# ESP32_ADC_DAC.net
KiCad netlist of a schematic drawn in Altium Designer
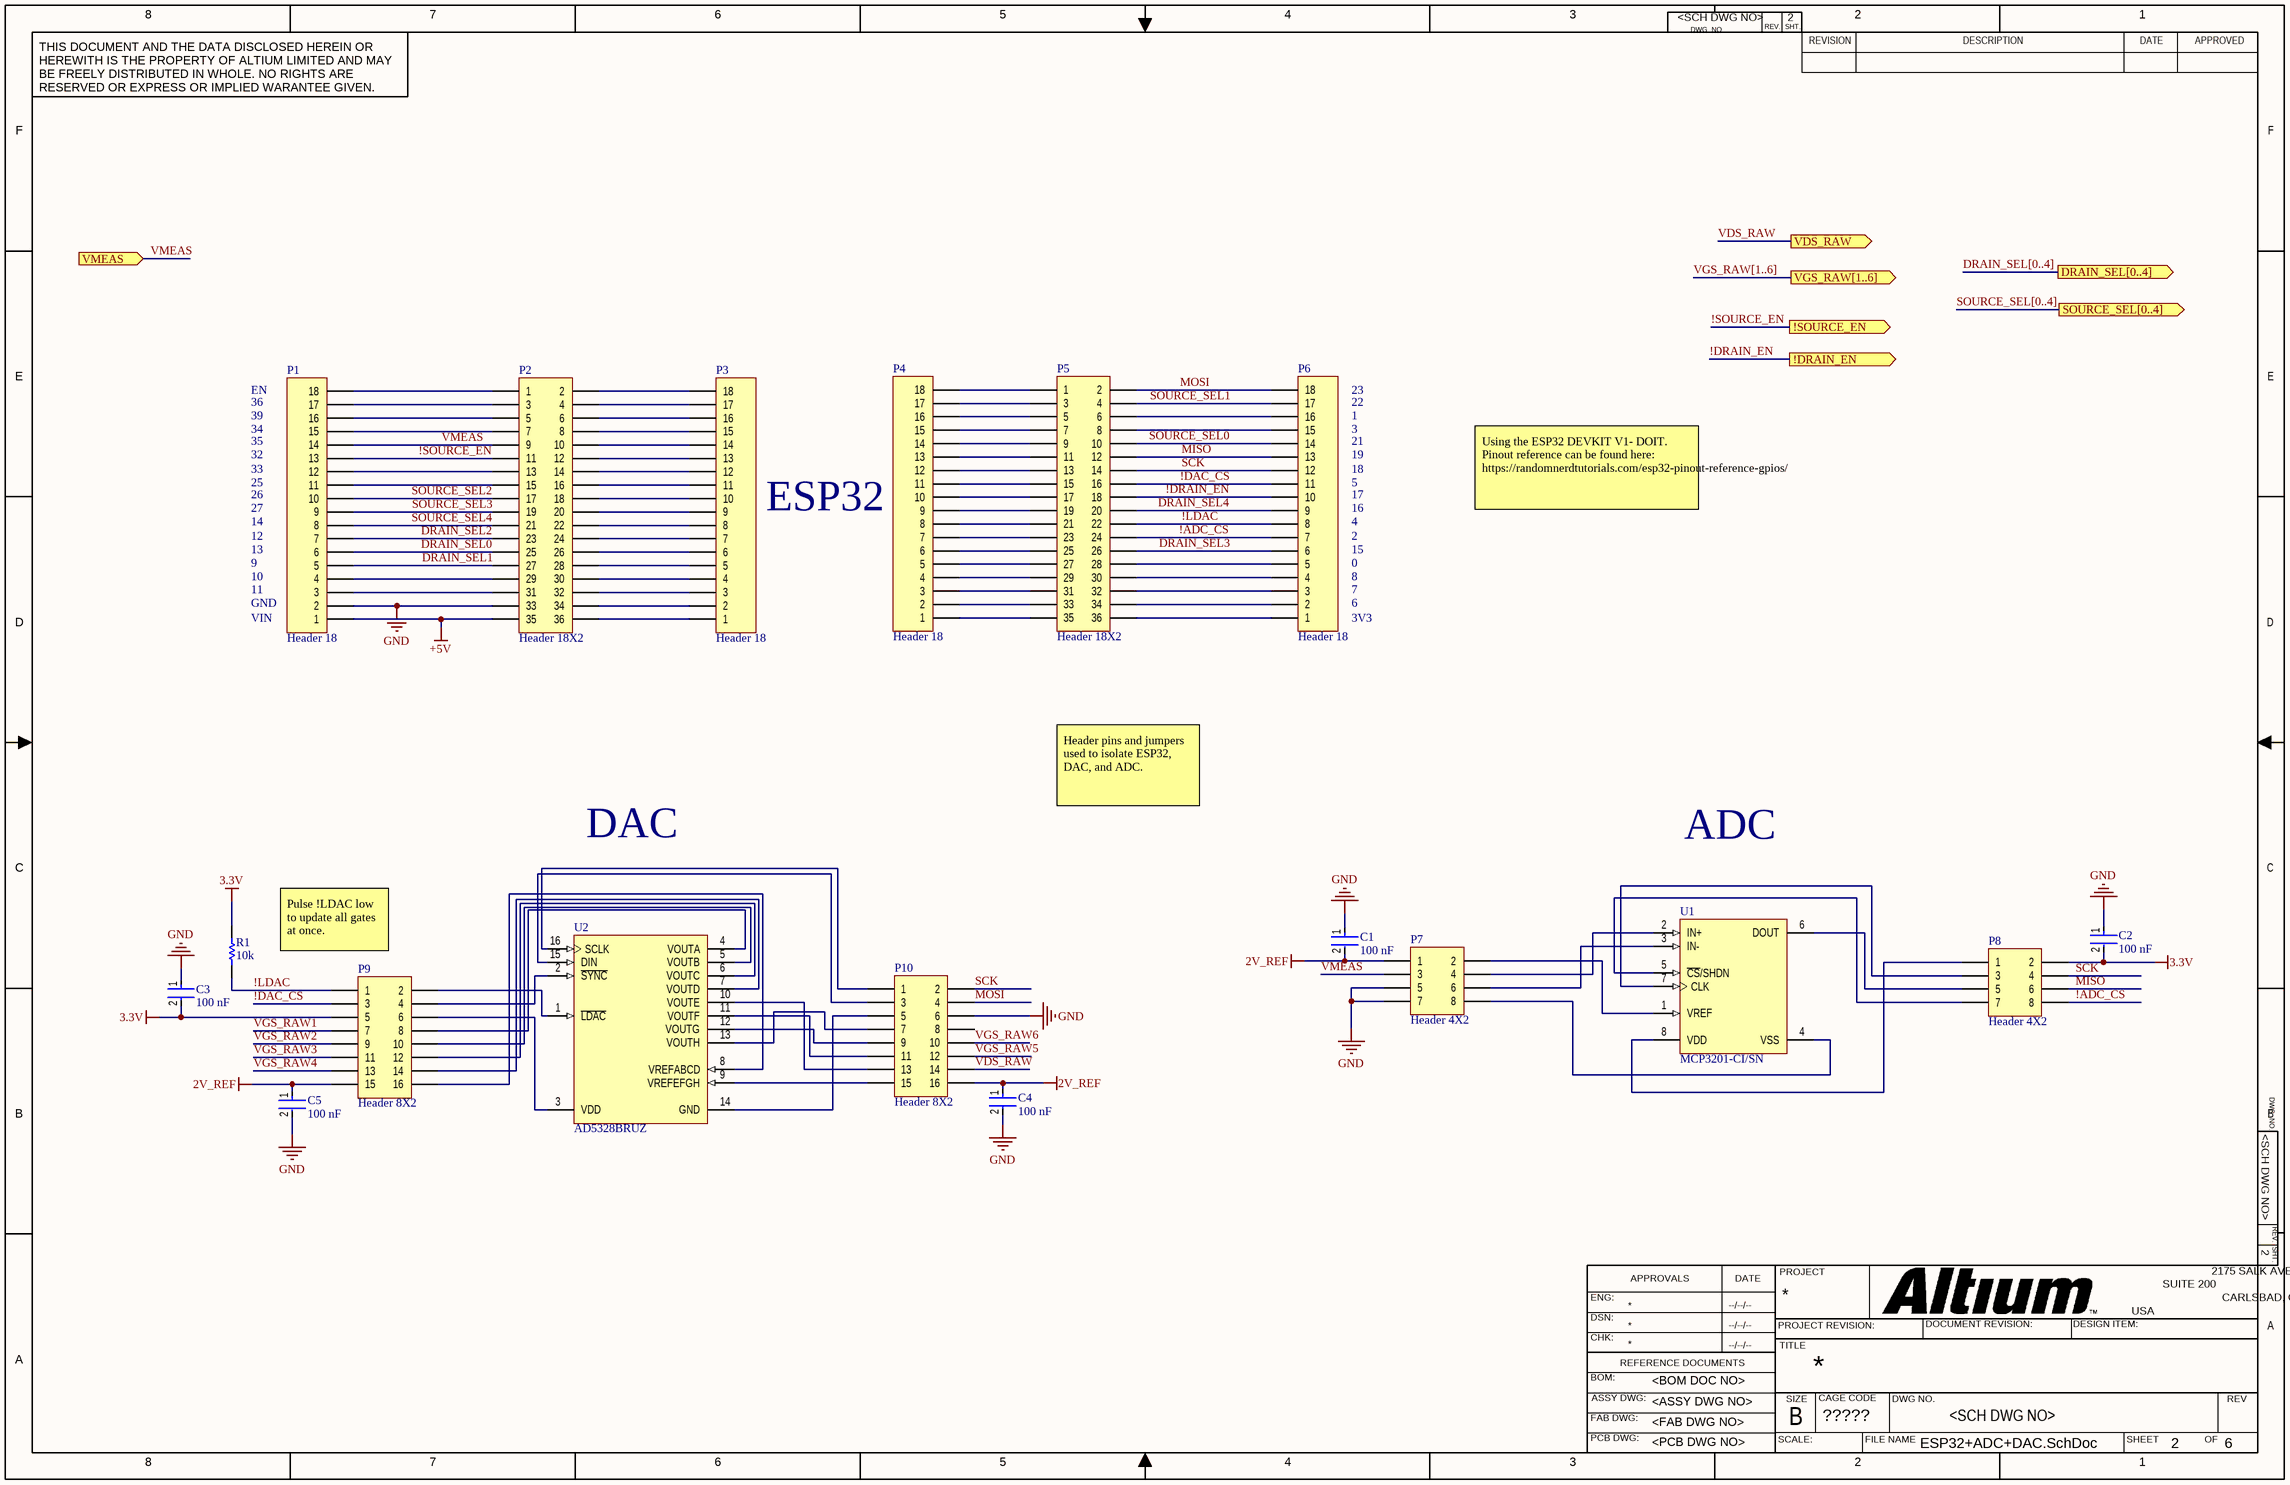
[diagram p0: ESP32+ADC+DAC.SchDoc]

(export (version "E")
  (design (tool "Eeschema 10.0.6"))
  (components
    (comp (ref "C1")
      (value "100 nF")
      (footprint "FP-C0805C-DN-MFG")
      (description "CAP CER 0.1UF 50V X7R 0805")
      (fields
        (field (name "MANUFACTURER PART NUMBER") "C0805C104K5RACTU")
        (field (name "MANUFACTURER") "KEMET")
      )
      (libsource (lib "Altium Content Vault") (part "b4654b650e69147ec39a6b967a45e02"))
    )
    (comp (ref "C2")
      (value "100 nF")
      (footprint "FP-C0805C-DN-MFG")
      (description "CAP CER 0.1UF 50V X7R 0805")
      (fields
        (field (name "MANUFACTURER PART NUMBER") "C0805C104K5RACTU")
        (field (name "MANUFACTURER") "KEMET")
      )
      (libsource (lib "Altium Content Vault") (part "b4654b650e69147ec39a6b967a45e02"))
    )
    (comp (ref "C3")
      (value "100 nF")
      (footprint "FP-C0805C-DN-MFG")
      (description "CAP CER 0.1UF 50V X7R 0805")
      (fields
        (field (name "MANUFACTURER PART NUMBER") "C0805C104K5RACTU")
        (field (name "MANUFACTURER") "KEMET")
      )
      (libsource (lib "Altium Content Vault") (part "b4654b650e69147ec39a6b967a45e02"))
    )
    (comp (ref "C4")
      (value "100 nF")
      (footprint "FP-C0805C-DN-MFG")
      (description "CAP CER 0.1UF 50V X7R 0805")
      (fields
        (field (name "MANUFACTURER PART NUMBER") "C0805C104K5RACTU")
        (field (name "MANUFACTURER") "KEMET")
      )
      (libsource (lib "Altium Content Vault") (part "b4654b650e69147ec39a6b967a45e02"))
    )
    (comp (ref "C5")
      (value "100 nF")
      (footprint "FP-C0805C-DN-MFG")
      (description "CAP CER 0.1UF 50V X7R 0805")
      (fields
        (field (name "MANUFACTURER PART NUMBER") "C0805C104K5RACTU")
        (field (name "MANUFACTURER") "KEMET")
      )
      (libsource (lib "Altium Content Vault") (part "b4654b650e69147ec39a6b967a45e02"))
    )
    (comp (ref "P1")
      (value "Header 18")
      (footprint "HDR1X18")
      (description "Header, 18-Pin")
      (fields (field (name "PUBLISHER") "Altium Limited"))
      (libsource (lib "") (part "Header 18_1"))
    )
    (comp (ref "P2")
      (value "Header 18X2")
      (footprint "HDR2X18")
      (description "Header, 18-Pin, Dual row")
      (fields (field (name "PUBLISHER") "Altium Limited"))
      (libsource (lib "Miscellaneous Connectors") (part "Header 18X2"))
    )
    (comp (ref "P3")
      (value "Header 18")
      (footprint "HDR1X18")
      (description "Header, 18-Pin")
      (fields (field (name "PUBLISHER") "Altium Limited"))
      (libsource (lib "Miscellaneous Connectors") (part "Header 18"))
    )
    (comp (ref "P4")
      (value "Header 18")
      (footprint "HDR1X18")
      (description "Header, 18-Pin")
      (fields (field (name "PUBLISHER") "Altium Limited"))
      (libsource (lib "") (part "Header 18_1"))
    )
    (comp (ref "P5")
      (value "Header 18X2")
      (footprint "HDR2X18")
      (description "Header, 18-Pin, Dual row")
      (fields (field (name "PUBLISHER") "Altium Limited"))
      (libsource (lib "Miscellaneous Connectors") (part "Header 18X2"))
    )
    (comp (ref "P6")
      (value "Header 18")
      (footprint "HDR1X18")
      (description "Header, 18-Pin")
      (fields (field (name "PUBLISHER") "Altium Limited"))
      (libsource (lib "Miscellaneous Connectors") (part "Header 18"))
    )
    (comp (ref "P7")
      (value "Header 4X2")
      (footprint "HDR2X4")
      (description "Header, 4-Pin, Dual row")
      (fields (field (name "PUBLISHER") "Altium Limited"))
      (libsource (lib "Miscellaneous Connectors") (part "Header 4X2"))
    )
    (comp (ref "P8")
      (value "Header 4X2")
      (footprint "HDR2X4")
      (description "Header, 4-Pin, Dual row")
      (fields (field (name "PUBLISHER") "Altium Limited"))
      (libsource (lib "Miscellaneous Connectors") (part "Header 4X2"))
    )
    (comp (ref "P9")
      (value "Header 8X2")
      (footprint "HDR2X8")
      (description "Header, 8-Pin, Dual row")
      (fields (field (name "PUBLISHER") "Altium Limited"))
      (libsource (lib "Miscellaneous Connectors") (part "Header 8X2"))
    )
    (comp (ref "P10")
      (value "Header 8X2")
      (footprint "HDR2X8")
      (description "Header, 8-Pin, Dual row")
      (fields (field (name "PUBLISHER") "Altium Limited"))
      (libsource (lib "Miscellaneous Connectors") (part "Header 8X2"))
    )
    (comp (ref "R1")
      (value "10k")
      (footprint "RESC2013X60X35NL10T20")
      (description "Chip Resistor, 10 KOhm, +/- 1%, 0.125 W, -55 to 155 degC, 0805 (2012 Metric), RoHS, Tape and Reel")
      (fields (field (name "MANUFACTURER") "Yageo"))
      (libsource (lib "Altium Content Vault") (part "RES-2"))
    )
    (comp (ref "U1")
      (value "MCP3201-CI/SN")
      (footprint "SOIC-SN8_L")
      (libsource (lib "Altium Content Vault") (part "CON-ADC-MCP3001-8"))
    )
    (comp (ref "U2")
      (value "AD5328BRUZ")
      (footprint "RU-16_L")
      (fields (field (name "GENERIC PART NUMBER") "AD5328") (field (name "MANUFACTURER") "Analog Devices"))
      (libsource (lib "Altium Content Vault") (part "ADI-AD5328-RU-16"))
    )
  )
  (nets
    (net (code "1") (name "+5V") (class "Default")
      (node (ref "P1") (pin "1") (pinfunction "1_1") (pintype "passive"))
      (node (ref "P2") (pin "35") (pinfunction "35_35") (pintype "passive"))
    )
    (net (code "2") (name "/!ADC_CS") (class "Default")
      (node (ref "P5") (pin "24") (pinfunction "24_24") (pintype "passive"))
      (node (ref "P6") (pin "7") (pinfunction "7_7") (pintype "passive"))
      (node (ref "P8") (pin "8") (pinfunction "8_8") (pintype "passive"))
    )
    (net (code "3") (name "/!DAC_CS") (class "Default")
      (node (ref "P5") (pin "16") (pinfunction "16_16") (pintype "passive"))
      (node (ref "P6") (pin "11") (pinfunction "11_11") (pintype "passive"))
      (node (ref "P9") (pin "3") (pinfunction "3_3") (pintype "passive"))
    )
    (net (code "4") (name "/!DRAIN_EN") (class "Default")
      (node (ref "P5") (pin "18") (pinfunction "18_18") (pintype "passive"))
      (node (ref "P6") (pin "10") (pinfunction "10_10") (pintype "passive"))
    )
    (net (code "5") (name "/!LDAC") (class "Default")
      (node (ref "P5") (pin "22") (pinfunction "22_22") (pintype "passive"))
      (node (ref "P6") (pin "8") (pinfunction "8_8") (pintype "passive"))
      (node (ref "P9") (pin "1") (pinfunction "1_1") (pintype "passive"))
      (node (ref "R1") (pin "1") (pinfunction "1_1") (pintype "passive"))
    )
    (net (code "6") (name "/!SOURCE_EN") (class "Default")
      (node (ref "P1") (pin "13") (pinfunction "13_13") (pintype "passive"))
      (node (ref "P2") (pin "11") (pinfunction "11_11") (pintype "passive"))
    )
    (net (code "7") (name "/DRAIN_SEL0") (class "Default")
      (node (ref "P1") (pin "6") (pinfunction "6_6") (pintype "passive"))
      (node (ref "P2") (pin "25") (pinfunction "25_25") (pintype "passive"))
    )
    (net (code "8") (name "/DRAIN_SEL1") (class "Default")
      (node (ref "P1") (pin "5") (pinfunction "5_5") (pintype "passive"))
      (node (ref "P2") (pin "27") (pinfunction "27_27") (pintype "passive"))
    )
    (net (code "9") (name "/DRAIN_SEL2") (class "Default")
      (node (ref "P1") (pin "7") (pinfunction "7_7") (pintype "passive"))
      (node (ref "P2") (pin "23") (pinfunction "23_23") (pintype "passive"))
    )
    (net (code "10") (name "/DRAIN_SEL3") (class "Default")
      (node (ref "P5") (pin "26") (pinfunction "26_26") (pintype "passive"))
      (node (ref "P6") (pin "6") (pinfunction "6_6") (pintype "passive"))
    )
    (net (code "11") (name "/DRAIN_SEL4") (class "Default")
      (node (ref "P5") (pin "20") (pinfunction "20_20") (pintype "passive"))
      (node (ref "P6") (pin "9") (pinfunction "9_9") (pintype "passive"))
    )
    (net (code "13") (name "/MISO") (class "Default")
      (node (ref "P5") (pin "12") (pinfunction "12_12") (pintype "passive"))
      (node (ref "P6") (pin "13") (pinfunction "13_13") (pintype "passive"))
      (node (ref "P8") (pin "6") (pinfunction "6_6") (pintype "passive"))
    )
    (net (code "14") (name "/MOSI") (class "Default")
      (node (ref "P10") (pin "4") (pinfunction "4_4") (pintype "passive"))
      (node (ref "P5") (pin "2") (pinfunction "2_2") (pintype "passive"))
      (node (ref "P6") (pin "18") (pinfunction "18_18") (pintype "passive"))
    )
    (net (code "15") (name "/SCK") (class "Default")
      (node (ref "P10") (pin "2") (pinfunction "2_2") (pintype "passive"))
      (node (ref "P5") (pin "14") (pinfunction "14_14") (pintype "passive"))
      (node (ref "P6") (pin "12") (pinfunction "12_12") (pintype "passive"))
      (node (ref "P8") (pin "4") (pinfunction "4_4") (pintype "passive"))
    )
    (net (code "16") (name "/SOURCE_SEL0") (class "Default")
      (node (ref "P5") (pin "10") (pinfunction "10_10") (pintype "passive"))
      (node (ref "P6") (pin "14") (pinfunction "14_14") (pintype "passive"))
    )
    (net (code "17") (name "/SOURCE_SEL1") (class "Default")
      (node (ref "P5") (pin "4") (pinfunction "4_4") (pintype "passive"))
      (node (ref "P6") (pin "17") (pinfunction "17_17") (pintype "passive"))
    )
    (net (code "18") (name "/SOURCE_SEL2") (class "Default")
      (node (ref "P1") (pin "10") (pinfunction "10_10") (pintype "passive"))
      (node (ref "P2") (pin "17") (pinfunction "17_17") (pintype "passive"))
    )
    (net (code "19") (name "/SOURCE_SEL3") (class "Default")
      (node (ref "P1") (pin "9") (pinfunction "9_9") (pintype "passive"))
      (node (ref "P2") (pin "19") (pinfunction "19_19") (pintype "passive"))
    )
    (net (code "20") (name "/SOURCE_SEL4") (class "Default")
      (node (ref "P1") (pin "8") (pinfunction "8_8") (pintype "passive"))
      (node (ref "P2") (pin "21") (pinfunction "21_21") (pintype "passive"))
    )
    (net (code "22") (name "/VDS_RAW") (class "Default")
      (node (ref "P10") (pin "14") (pinfunction "14_14") (pintype "passive"))
    )
    (net (code "23") (name "/VGS_RAW1") (class "Default")
      (node (ref "P9") (pin "7") (pinfunction "7_7") (pintype "passive"))
    )
    (net (code "24") (name "/VGS_RAW2") (class "Default")
      (node (ref "P9") (pin "9") (pinfunction "9_9") (pintype "passive"))
    )
    (net (code "25") (name "/VGS_RAW3") (class "Default")
      (node (ref "P9") (pin "11") (pinfunction "11_11") (pintype "passive"))
    )
    (net (code "26") (name "/VGS_RAW4") (class "Default")
      (node (ref "P9") (pin "13") (pinfunction "13_13") (pintype "passive"))
    )
    (net (code "27") (name "/VGS_RAW5") (class "Default")
      (node (ref "P10") (pin "12") (pinfunction "12_12") (pintype "passive"))
    )
    (net (code "28") (name "/VGS_RAW6") (class "Default")
      (node (ref "P10") (pin "10") (pinfunction "10_10") (pintype "passive"))
    )
    (net (code "30") (name "/VMEAS") (class "Default")
      (node (ref "P1") (pin "14") (pinfunction "14_14") (pintype "passive"))
      (node (ref "P2") (pin "9") (pinfunction "9_9") (pintype "passive"))
      (node (ref "P7") (pin "3") (pinfunction "3_3") (pintype "passive"))
    )
    (net (code "31") (name "2V_REF") (class "Default")
      (node (ref "C1") (pin "2") (pinfunction "2_2") (pintype "passive"))
      (node (ref "C4") (pin "1") (pinfunction "1_1") (pintype "passive"))
      (node (ref "C5") (pin "1") (pinfunction "1_1") (pintype "passive"))
      (node (ref "P10") (pin "16") (pinfunction "16_16") (pintype "passive"))
      (node (ref "P7") (pin "1") (pinfunction "1_1") (pintype "passive"))
      (node (ref "P9") (pin "15") (pinfunction "15_15") (pintype "passive"))
    )
    (net (code "32") (name "3.3V") (class "Default")
      (node (ref "C2") (pin "2") (pinfunction "2_2") (pintype "passive"))
      (node (ref "C3") (pin "2") (pinfunction "2_2") (pintype "passive"))
      (node (ref "P8") (pin "2") (pinfunction "2_2") (pintype "passive"))
      (node (ref "P9") (pin "5") (pinfunction "5_5") (pintype "passive"))
      (node (ref "R1") (pin "2") (pinfunction "2_2") (pintype "passive"))
    )
    (net (code "33") (name "GND") (class "Default")
      (node (ref "C1") (pin "1") (pinfunction "1_1") (pintype "passive"))
      (node (ref "C2") (pin "1") (pinfunction "1_1") (pintype "passive"))
      (node (ref "C3") (pin "1") (pinfunction "1_1") (pintype "passive"))
      (node (ref "C4") (pin "2") (pinfunction "2_2") (pintype "passive"))
      (node (ref "C5") (pin "2") (pinfunction "2_2") (pintype "passive"))
      (node (ref "P1") (pin "2") (pinfunction "2_2") (pintype "passive"))
      (node (ref "P10") (pin "6") (pinfunction "6_6") (pintype "passive"))
      (node (ref "P2") (pin "33") (pinfunction "33_33") (pintype "passive"))
      (node (ref "P7") (pin "5") (pinfunction "5_5") (pintype "passive"))
      (node (ref "P7") (pin "7") (pinfunction "7_7") (pintype "passive"))
    )
    (net (code "34") (name "Net-(P1-Pad3)") (class "Default")
      (node (ref "P1") (pin "3") (pinfunction "3_3") (pintype "passive"))
      (node (ref "P2") (pin "31") (pinfunction "31_31") (pintype "passive"))
    )
    (net (code "35") (name "Net-(P1-Pad4)") (class "Default")
      (node (ref "P1") (pin "4") (pinfunction "4_4") (pintype "passive"))
      (node (ref "P2") (pin "29") (pinfunction "29_29") (pintype "passive"))
    )
    (net (code "36") (name "Net-(P1-Pad11)") (class "Default")
      (node (ref "P1") (pin "11") (pinfunction "11_11") (pintype "passive"))
      (node (ref "P2") (pin "15") (pinfunction "15_15") (pintype "passive"))
    )
    (net (code "37") (name "Net-(P1-Pad12)") (class "Default")
      (node (ref "P1") (pin "12") (pinfunction "12_12") (pintype "passive"))
      (node (ref "P2") (pin "13") (pinfunction "13_13") (pintype "passive"))
    )
    (net (code "38") (name "Net-(P1-Pad15)") (class "Default")
      (node (ref "P1") (pin "15") (pinfunction "15_15") (pintype "passive"))
      (node (ref "P2") (pin "7") (pinfunction "7_7") (pintype "passive"))
    )
    (net (code "39") (name "Net-(P1-Pad16)") (class "Default")
      (node (ref "P1") (pin "16") (pinfunction "16_16") (pintype "passive"))
      (node (ref "P2") (pin "5") (pinfunction "5_5") (pintype "passive"))
    )
    (net (code "40") (name "Net-(P1-Pad17)") (class "Default")
      (node (ref "P1") (pin "17") (pinfunction "17_17") (pintype "passive"))
      (node (ref "P2") (pin "3") (pinfunction "3_3") (pintype "passive"))
    )
    (net (code "41") (name "Net-(P1-Pad18)") (class "Default")
      (node (ref "P1") (pin "18") (pinfunction "18_18") (pintype "passive"))
      (node (ref "P2") (pin "1") (pinfunction "1_1") (pintype "passive"))
    )
    (net (code "42") (name "Net-(P2-Pad2)") (class "Default")
      (node (ref "P2") (pin "2") (pinfunction "2_2") (pintype "passive"))
      (node (ref "P3") (pin "18") (pinfunction "18_18") (pintype "passive"))
    )
    (net (code "43") (name "Net-(P2-Pad4)") (class "Default")
      (node (ref "P2") (pin "4") (pinfunction "4_4") (pintype "passive"))
      (node (ref "P3") (pin "17") (pinfunction "17_17") (pintype "passive"))
    )
    (net (code "44") (name "Net-(P2-Pad6)") (class "Default")
      (node (ref "P2") (pin "6") (pinfunction "6_6") (pintype "passive"))
      (node (ref "P3") (pin "16") (pinfunction "16_16") (pintype "passive"))
    )
    (net (code "45") (name "Net-(P2-Pad8)") (class "Default")
      (node (ref "P2") (pin "8") (pinfunction "8_8") (pintype "passive"))
      (node (ref "P3") (pin "15") (pinfunction "15_15") (pintype "passive"))
    )
    (net (code "46") (name "Net-(P2-Pad10)") (class "Default")
      (node (ref "P2") (pin "10") (pinfunction "10_10") (pintype "passive"))
      (node (ref "P3") (pin "14") (pinfunction "14_14") (pintype "passive"))
    )
    (net (code "47") (name "Net-(P2-Pad12)") (class "Default")
      (node (ref "P2") (pin "12") (pinfunction "12_12") (pintype "passive"))
      (node (ref "P3") (pin "13") (pinfunction "13_13") (pintype "passive"))
    )
    (net (code "48") (name "Net-(P2-Pad14)") (class "Default")
      (node (ref "P2") (pin "14") (pinfunction "14_14") (pintype "passive"))
      (node (ref "P3") (pin "12") (pinfunction "12_12") (pintype "passive"))
    )
    (net (code "49") (name "Net-(P2-Pad16)") (class "Default")
      (node (ref "P2") (pin "16") (pinfunction "16_16") (pintype "passive"))
      (node (ref "P3") (pin "11") (pinfunction "11_11") (pintype "passive"))
    )
    (net (code "50") (name "Net-(P2-Pad18)") (class "Default")
      (node (ref "P2") (pin "18") (pinfunction "18_18") (pintype "passive"))
      (node (ref "P3") (pin "10") (pinfunction "10_10") (pintype "passive"))
    )
    (net (code "51") (name "Net-(P2-Pad20)") (class "Default")
      (node (ref "P2") (pin "20") (pinfunction "20_20") (pintype "passive"))
      (node (ref "P3") (pin "9") (pinfunction "9_9") (pintype "passive"))
    )
    (net (code "52") (name "Net-(P2-Pad22)") (class "Default")
      (node (ref "P2") (pin "22") (pinfunction "22_22") (pintype "passive"))
      (node (ref "P3") (pin "8") (pinfunction "8_8") (pintype "passive"))
    )
    (net (code "53") (name "Net-(P2-Pad24)") (class "Default")
      (node (ref "P2") (pin "24") (pinfunction "24_24") (pintype "passive"))
      (node (ref "P3") (pin "7") (pinfunction "7_7") (pintype "passive"))
    )
    (net (code "54") (name "Net-(P2-Pad26)") (class "Default")
      (node (ref "P2") (pin "26") (pinfunction "26_26") (pintype "passive"))
      (node (ref "P3") (pin "6") (pinfunction "6_6") (pintype "passive"))
    )
    (net (code "55") (name "Net-(P2-Pad28)") (class "Default")
      (node (ref "P2") (pin "28") (pinfunction "28_28") (pintype "passive"))
      (node (ref "P3") (pin "5") (pinfunction "5_5") (pintype "passive"))
    )
    (net (code "56") (name "Net-(P2-Pad30)") (class "Default")
      (node (ref "P2") (pin "30") (pinfunction "30_30") (pintype "passive"))
      (node (ref "P3") (pin "4") (pinfunction "4_4") (pintype "passive"))
    )
    (net (code "57") (name "Net-(P2-Pad32)") (class "Default")
      (node (ref "P2") (pin "32") (pinfunction "32_32") (pintype "passive"))
      (node (ref "P3") (pin "3") (pinfunction "3_3") (pintype "passive"))
    )
    (net (code "58") (name "Net-(P2-Pad34)") (class "Default")
      (node (ref "P2") (pin "34") (pinfunction "34_34") (pintype "passive"))
      (node (ref "P3") (pin "2") (pinfunction "2_2") (pintype "passive"))
    )
    (net (code "59") (name "Net-(P2-Pad36)") (class "Default")
      (node (ref "P2") (pin "36") (pinfunction "36_36") (pintype "passive"))
      (node (ref "P3") (pin "1") (pinfunction "1_1") (pintype "passive"))
    )
    (net (code "60") (name "Net-(P4-Pad1)") (class "Default")
      (node (ref "P4") (pin "1") (pinfunction "1_1") (pintype "passive"))
      (node (ref "P5") (pin "35") (pinfunction "35_35") (pintype "passive"))
    )
    (net (code "61") (name "Net-(P4-Pad2)") (class "Default")
      (node (ref "P4") (pin "2") (pinfunction "2_2") (pintype "passive"))
      (node (ref "P5") (pin "33") (pinfunction "33_33") (pintype "passive"))
    )
    (net (code "62") (name "Net-(P4-Pad3)") (class "Default")
      (node (ref "P4") (pin "3") (pinfunction "3_3") (pintype "passive"))
      (node (ref "P5") (pin "31") (pinfunction "31_31") (pintype "passive"))
    )
    (net (code "63") (name "Net-(P4-Pad4)") (class "Default")
      (node (ref "P4") (pin "4") (pinfunction "4_4") (pintype "passive"))
      (node (ref "P5") (pin "29") (pinfunction "29_29") (pintype "passive"))
    )
    (net (code "64") (name "Net-(P4-Pad5)") (class "Default")
      (node (ref "P4") (pin "5") (pinfunction "5_5") (pintype "passive"))
      (node (ref "P5") (pin "27") (pinfunction "27_27") (pintype "passive"))
    )
    (net (code "65") (name "Net-(P4-Pad6)") (class "Default")
      (node (ref "P4") (pin "6") (pinfunction "6_6") (pintype "passive"))
      (node (ref "P5") (pin "25") (pinfunction "25_25") (pintype "passive"))
    )
    (net (code "66") (name "Net-(P4-Pad7)") (class "Default")
      (node (ref "P4") (pin "7") (pinfunction "7_7") (pintype "passive"))
      (node (ref "P5") (pin "23") (pinfunction "23_23") (pintype "passive"))
    )
    (net (code "67") (name "Net-(P4-Pad8)") (class "Default")
      (node (ref "P4") (pin "8") (pinfunction "8_8") (pintype "passive"))
      (node (ref "P5") (pin "21") (pinfunction "21_21") (pintype "passive"))
    )
    (net (code "68") (name "Net-(P4-Pad9)") (class "Default")
      (node (ref "P4") (pin "9") (pinfunction "9_9") (pintype "passive"))
      (node (ref "P5") (pin "19") (pinfunction "19_19") (pintype "passive"))
    )
    (net (code "69") (name "Net-(P4-Pad10)") (class "Default")
      (node (ref "P4") (pin "10") (pinfunction "10_10") (pintype "passive"))
      (node (ref "P5") (pin "17") (pinfunction "17_17") (pintype "passive"))
    )
    (net (code "70") (name "Net-(P4-Pad11)") (class "Default")
      (node (ref "P4") (pin "11") (pinfunction "11_11") (pintype "passive"))
      (node (ref "P5") (pin "15") (pinfunction "15_15") (pintype "passive"))
    )
    (net (code "71") (name "Net-(P4-Pad12)") (class "Default")
      (node (ref "P4") (pin "12") (pinfunction "12_12") (pintype "passive"))
      (node (ref "P5") (pin "13") (pinfunction "13_13") (pintype "passive"))
    )
    (net (code "72") (name "Net-(P4-Pad13)") (class "Default")
      (node (ref "P4") (pin "13") (pinfunction "13_13") (pintype "passive"))
      (node (ref "P5") (pin "11") (pinfunction "11_11") (pintype "passive"))
    )
    (net (code "73") (name "Net-(P4-Pad14)") (class "Default")
      (node (ref "P4") (pin "14") (pinfunction "14_14") (pintype "passive"))
      (node (ref "P5") (pin "9") (pinfunction "9_9") (pintype "passive"))
    )
    (net (code "74") (name "Net-(P4-Pad15)") (class "Default")
      (node (ref "P4") (pin "15") (pinfunction "15_15") (pintype "passive"))
      (node (ref "P5") (pin "7") (pinfunction "7_7") (pintype "passive"))
    )
    (net (code "75") (name "Net-(P4-Pad16)") (class "Default")
      (node (ref "P4") (pin "16") (pinfunction "16_16") (pintype "passive"))
      (node (ref "P5") (pin "5") (pinfunction "5_5") (pintype "passive"))
    )
    (net (code "76") (name "Net-(P4-Pad17)") (class "Default")
      (node (ref "P4") (pin "17") (pinfunction "17_17") (pintype "passive"))
      (node (ref "P5") (pin "3") (pinfunction "3_3") (pintype "passive"))
    )
    (net (code "77") (name "Net-(P4-Pad18)") (class "Default")
      (node (ref "P4") (pin "18") (pinfunction "18_18") (pintype "passive"))
      (node (ref "P5") (pin "1") (pinfunction "1_1") (pintype "passive"))
    )
    (net (code "78") (name "Net-(P5-Pad6)") (class "Default")
      (node (ref "P5") (pin "6") (pinfunction "6_6") (pintype "passive"))
      (node (ref "P6") (pin "16") (pinfunction "16_16") (pintype "passive"))
    )
    (net (code "79") (name "Net-(P5-Pad8)") (class "Default")
      (node (ref "P5") (pin "8") (pinfunction "8_8") (pintype "passive"))
      (node (ref "P6") (pin "15") (pinfunction "15_15") (pintype "passive"))
    )
    (net (code "80") (name "Net-(P5-Pad28)") (class "Default")
      (node (ref "P5") (pin "28") (pinfunction "28_28") (pintype "passive"))
      (node (ref "P6") (pin "5") (pinfunction "5_5") (pintype "passive"))
    )
    (net (code "81") (name "Net-(P5-Pad30)") (class "Default")
      (node (ref "P5") (pin "30") (pinfunction "30_30") (pintype "passive"))
      (node (ref "P6") (pin "4") (pinfunction "4_4") (pintype "passive"))
    )
    (net (code "82") (name "Net-(P5-Pad32)") (class "Default")
      (node (ref "P5") (pin "32") (pinfunction "32_32") (pintype "passive"))
      (node (ref "P6") (pin "3") (pinfunction "3_3") (pintype "passive"))
    )
    (net (code "83") (name "Net-(P5-Pad34)") (class "Default")
      (node (ref "P5") (pin "34") (pinfunction "34_34") (pintype "passive"))
      (node (ref "P6") (pin "2") (pinfunction "2_2") (pintype "passive"))
    )
    (net (code "84") (name "Net-(P5-Pad36)") (class "Default")
      (node (ref "P5") (pin "36") (pinfunction "36_36") (pintype "passive"))
      (node (ref "P6") (pin "1") (pinfunction "1_1") (pintype "passive"))
    )
    (net (code "85") (name "Net-(U1-CLK)") (class "Default")
      (node (ref "P8") (pin "3") (pinfunction "3_3") (pintype "passive"))
      (node (ref "U1") (pin "7") (pinfunction "CLK_7") (pintype "input"))
    )
    (net (code "86") (name "Net-(U1-DOUT)") (class "Default")
      (node (ref "P8") (pin "5") (pinfunction "5_5") (pintype "passive"))
      (node (ref "U1") (pin "6") (pinfunction "DOUT_6") (pintype "tri_state"))
    )
    (net (code "87") (name "Net-(U1-IN+)") (class "Default")
      (node (ref "P7") (pin "4") (pinfunction "4_4") (pintype "passive"))
      (node (ref "U1") (pin "2") (pinfunction "IN+_2") (pintype "input"))
    )
    (net (code "88") (name "Net-(U1-IN-)") (class "Default")
      (node (ref "P7") (pin "6") (pinfunction "6_6") (pintype "passive"))
      (node (ref "U1") (pin "3") (pinfunction "IN-_3") (pintype "input"))
    )
    (net (code "89") (name "Net-(U1-VDD)") (class "Default")
      (node (ref "P8") (pin "1") (pinfunction "1_1") (pintype "passive"))
      (node (ref "U1") (pin "8") (pinfunction "VDD_8") (pintype "power_in"))
    )
    (net (code "90") (name "Net-(U1-VREF)") (class "Default")
      (node (ref "P7") (pin "2") (pinfunction "2_2") (pintype "passive"))
      (node (ref "U1") (pin "1") (pinfunction "VREF_1") (pintype "input"))
    )
    (net (code "91") (name "Net-(U1-VSS)") (class "Default")
      (node (ref "P7") (pin "8") (pinfunction "8_8") (pintype "passive"))
      (node (ref "U1") (pin "4") (pinfunction "VSS_4") (pintype "power_in"))
    )
    (net (code "92") (name "Net-(U1-~{CS}{slash}SHDN)") (class "Default")
      (node (ref "P8") (pin "7") (pinfunction "7_7") (pintype "passive"))
      (node (ref "U1") (pin "5") (pinfunction "~{CS}/SHDN_5") (pintype "input"))
    )
    (net (code "93") (name "Net-(U2-DIN)") (class "Default")
      (node (ref "P10") (pin "3") (pinfunction "3_3") (pintype "passive"))
      (node (ref "U2") (pin "15") (pinfunction "DIN_15") (pintype "input"))
    )
    (net (code "94") (name "Net-(U2-GND)") (class "Default")
      (node (ref "P10") (pin "5") (pinfunction "5_5") (pintype "passive"))
      (node (ref "U2") (pin "14") (pinfunction "GND_14") (pintype "power_in"))
    )
    (net (code "95") (name "Net-(U2-SCLK)") (class "Default")
      (node (ref "P10") (pin "1") (pinfunction "1_1") (pintype "passive"))
      (node (ref "U2") (pin "16") (pinfunction "SCLK_16") (pintype "input"))
    )
    (net (code "96") (name "Net-(U2-VDD)") (class "Default")
      (node (ref "P9") (pin "6") (pinfunction "6_6") (pintype "passive"))
      (node (ref "U2") (pin "3") (pinfunction "VDD_3") (pintype "power_in"))
    )
    (net (code "97") (name "Net-(U2-VOUTA)") (class "Default")
      (node (ref "P9") (pin "8") (pinfunction "8_8") (pintype "passive"))
      (node (ref "U2") (pin "4") (pinfunction "VOUTA_4") (pintype "tri_state"))
    )
    (net (code "98") (name "Net-(U2-VOUTB)") (class "Default")
      (node (ref "P9") (pin "10") (pinfunction "10_10") (pintype "passive"))
      (node (ref "U2") (pin "5") (pinfunction "VOUTB_5") (pintype "tri_state"))
    )
    (net (code "99") (name "Net-(U2-VOUTC)") (class "Default")
      (node (ref "P9") (pin "12") (pinfunction "12_12") (pintype "passive"))
      (node (ref "U2") (pin "6") (pinfunction "VOUTC_6") (pintype "tri_state"))
    )
    (net (code "100") (name "Net-(U2-VOUTD)") (class "Default")
      (node (ref "P9") (pin "14") (pinfunction "14_14") (pintype "passive"))
      (node (ref "U2") (pin "7") (pinfunction "VOUTD_7") (pintype "tri_state"))
    )
    (net (code "101") (name "Net-(U2-VOUTE)") (class "Default")
      (node (ref "P10") (pin "13") (pinfunction "13_13") (pintype "passive"))
      (node (ref "U2") (pin "10") (pinfunction "VOUTE_10") (pintype "tri_state"))
    )
    (net (code "102") (name "Net-(U2-VOUTF)") (class "Default")
      (node (ref "P10") (pin "11") (pinfunction "11_11") (pintype "passive"))
      (node (ref "U2") (pin "11") (pinfunction "VOUTF_11") (pintype "tri_state"))
    )
    (net (code "103") (name "Net-(U2-VOUTG)") (class "Default")
      (node (ref "P10") (pin "9") (pinfunction "9_9") (pintype "passive"))
      (node (ref "U2") (pin "12") (pinfunction "VOUTG_12") (pintype "tri_state"))
    )
    (net (code "104") (name "Net-(U2-VOUTH)") (class "Default")
      (node (ref "P10") (pin "7") (pinfunction "7_7") (pintype "passive"))
      (node (ref "U2") (pin "13") (pinfunction "VOUTH_13") (pintype "tri_state"))
    )
    (net (code "105") (name "Net-(U2-VREFABCD)") (class "Default")
      (node (ref "P9") (pin "16") (pinfunction "16_16") (pintype "passive"))
      (node (ref "U2") (pin "8") (pinfunction "VREFABCD_8") (pintype "input"))
    )
    (net (code "106") (name "Net-(U2-VREFEFGH)") (class "Default")
      (node (ref "P10") (pin "15") (pinfunction "15_15") (pintype "passive"))
      (node (ref "U2") (pin "9") (pinfunction "VREFEFGH_9") (pintype "input"))
    )
    (net (code "107") (name "Net-(U2-~{LDAC})") (class "Default")
      (node (ref "P9") (pin "2") (pinfunction "2_2") (pintype "passive"))
      (node (ref "U2") (pin "1") (pinfunction "~{LDAC}_1") (pintype "input"))
    )
    (net (code "108") (name "Net-(U2-~{SYNC})") (class "Default")
      (node (ref "P9") (pin "4") (pinfunction "4_4") (pintype "passive"))
      (node (ref "U2") (pin "2") (pinfunction "~{SYNC}_2") (pintype "input"))
    )
    (net (code "109") (name "unconnected-(P10-Pad8)") (class "Default")
      (node (ref "P10") (pin "8") (pinfunction "8_8") (pintype "passive"))
    )
  )
)
